# Audio_Tianfeng2.net
KiCad netlist of a schematic drawn in EAGLE
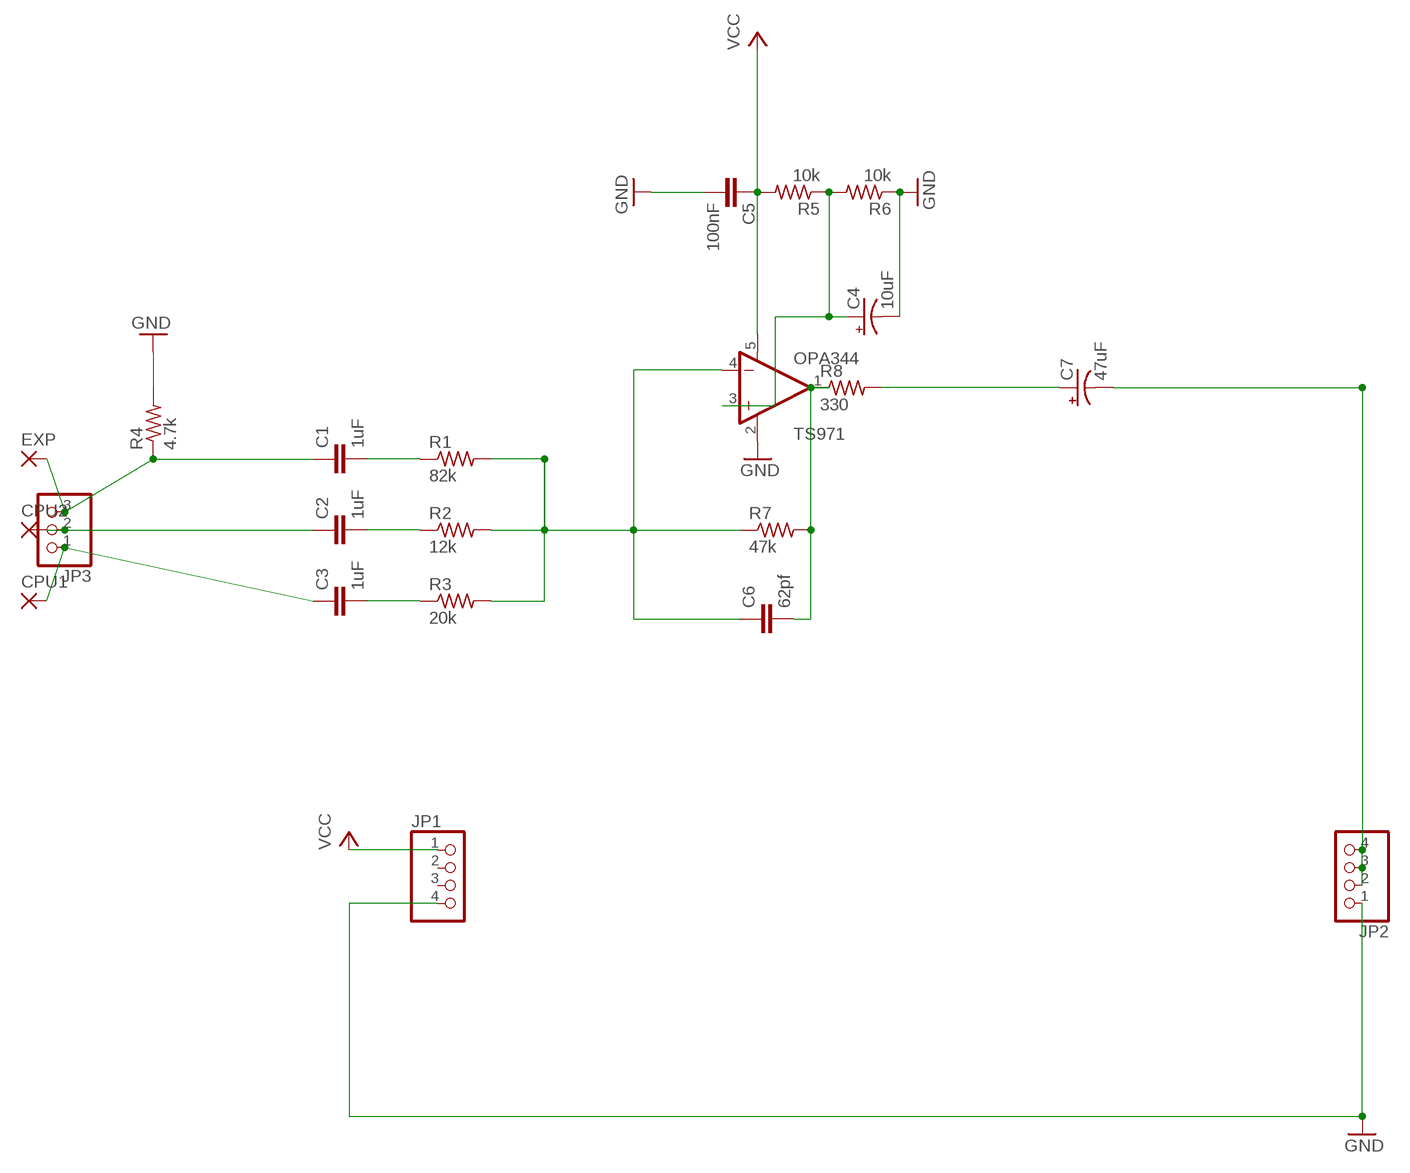
[diagram p0: schematic, sheet 1]

(export (version "E")
  (design (tool "Eeschema 10.0.6"))
  (components
    (comp (ref "C1")
      (value "1uF")
      (footprint "eagle-import:C0603K")
      (libsource (lib "eagle-import") (part "C-EUC0603K"))
    )
    (comp (ref "C2")
      (value "1uF")
      (footprint "eagle-import:C0603K")
      (libsource (lib "eagle-import") (part "C-EUC0603K"))
    )
    (comp (ref "C3")
      (value "1uF")
      (footprint "eagle-import:C0603K")
      (libsource (lib "eagle-import") (part "C-EUC0603K"))
    )
    (comp (ref "C4")
      (value "10uF")
      (footprint "eagle-import:153CLV-0405")
      (libsource (lib "eagle-import") (part "CPOL-US153CLV-0405"))
    )
    (comp (ref "C5")
      (value "100nF")
      (footprint "eagle-import:C0603K")
      (libsource (lib "eagle-import") (part "C-EUC0603K"))
    )
    (comp (ref "C6")
      (value "62pf")
      (footprint "eagle-import:C0603K")
      (libsource (lib "eagle-import") (part "C-EUC0603K"))
    )
    (comp (ref "C7")
      (value "47uF")
      (footprint "eagle-import:153CLV-0405")
      (libsource (lib "eagle-import") (part "CPOL-US153CLV-0405"))
    )
    (comp (ref "CPU1")
      (value "SMD2")
      (footprint "eagle-import:SMD1,27-2,54")
      (libsource (lib "eagle-import") (part "SMD2"))
    )
    (comp (ref "CPU2")
      (value "SMD2")
      (footprint "eagle-import:SMD1,27-2,54")
      (libsource (lib "eagle-import") (part "SMD2"))
    )
    (comp (ref "EXP")
      (value "SMD2")
      (footprint "eagle-import:SMD1,27-2,54")
      (libsource (lib "eagle-import") (part "SMD2"))
    )
    (comp (ref "JP1")
      (value "PINHD-1X04_2.54-S")
      (footprint "eagle-import:1X04-S")
      (libsource (lib "eagle-import") (part "PINHD-1X04_2.54-S"))
    )
    (comp (ref "JP2")
      (value "PINHD-1X04_2.54-S")
      (footprint "eagle-import:1X04-S")
      (libsource (lib "eagle-import") (part "PINHD-1X04_2.54-S"))
    )
    (comp (ref "JP3")
      (value "PINHD-1X03_2.54-S")
      (footprint "eagle-import:1X03-S")
      (libsource (lib "eagle-import") (part "PINHD-1X03_2.54-S"))
    )
    (comp (ref "R1")
      (value "82k")
      (footprint "eagle-import:R0603")
      (libsource (lib "eagle-import") (part "R-US_R0603"))
    )
    (comp (ref "R2")
      (value "12k")
      (footprint "eagle-import:R0603")
      (libsource (lib "eagle-import") (part "R-US_R0603"))
    )
    (comp (ref "R3")
      (value "20k")
      (footprint "eagle-import:R0603")
      (libsource (lib "eagle-import") (part "R-US_R0603"))
    )
    (comp (ref "R4")
      (value "4.7k")
      (footprint "eagle-import:R0603")
      (libsource (lib "eagle-import") (part "R-US_R0603"))
    )
    (comp (ref "R5")
      (value "10k")
      (footprint "eagle-import:R0603")
      (libsource (lib "eagle-import") (part "R-US_R0603"))
    )
    (comp (ref "R6")
      (value "10k")
      (footprint "eagle-import:R0603")
      (libsource (lib "eagle-import") (part "R-US_R0603"))
    )
    (comp (ref "R7")
      (value "47k")
      (footprint "eagle-import:R0603")
      (libsource (lib "eagle-import") (part "R-US_R0603"))
    )
    (comp (ref "R8")
      (value "330")
      (footprint "eagle-import:R0603")
      (libsource (lib "eagle-import") (part "R-US_R0603"))
    )
    (comp (ref "TS971")
      (value "OPA344")
      (footprint "eagle-import:SOT23-5")
      (libsource (lib "eagle-import") (part "OPA344"))
    )
  )
  (nets
    (net (code "1") (name "GND") (class "Default")
      (node (ref "C4") (pin "-") (pinfunction "-_-") (pintype "passive"))
      (node (ref "C5") (pin "2") (pinfunction "2_2") (pintype "passive"))
      (node (ref "JP1") (pin "4") (pinfunction "4_4") (pintype "passive"))
      (node (ref "JP2") (pin "1") (pinfunction "1_1") (pintype "passive"))
      (node (ref "R4") (pin "2") (pinfunction "2_2") (pintype "passive"))
      (node (ref "R6") (pin "1") (pinfunction "1_1") (pintype "passive"))
      (node (ref "TS971") (pin "2") (pinfunction "V-_2") (pintype "power_in"))
    )
    (net (code "2") (name "Net-(C1-Pad2)") (class "Default")
      (node (ref "C1") (pin "2") (pinfunction "2_2") (pintype "passive"))
      (node (ref "R1") (pin "1") (pinfunction "1_1") (pintype "passive"))
    )
    (net (code "3") (name "Net-(C2-Pad2)") (class "Default")
      (node (ref "C2") (pin "2") (pinfunction "2_2") (pintype "passive"))
      (node (ref "R2") (pin "1") (pinfunction "1_1") (pintype "passive"))
    )
    (net (code "4") (name "Net-(C3-Pad2)") (class "Default")
      (node (ref "C3") (pin "2") (pinfunction "2_2") (pintype "passive"))
      (node (ref "R3") (pin "1") (pinfunction "1_1") (pintype "passive"))
    )
    (net (code "5") (name "Net-(C7-Pad+)") (class "Default")
      (node (ref "C7") (pin "+") (pinfunction "+_+") (pintype "passive"))
      (node (ref "R8") (pin "2") (pinfunction "2_2") (pintype "passive"))
    )
    (net (code "6") (name "Net-(C7-Pad-)") (class "Default")
      (node (ref "C7") (pin "-") (pinfunction "-_-") (pintype "passive"))
      (node (ref "JP2") (pin "2") (pinfunction "2_2") (pintype "passive"))
      (node (ref "JP2") (pin "3") (pinfunction "3_3") (pintype "passive"))
      (node (ref "JP2") (pin "4") (pinfunction "4_4") (pintype "passive"))
    )
    (net (code "7") (name "Net-(CPU1-P)") (class "Default")
      (node (ref "C3") (pin "1") (pinfunction "1_1") (pintype "passive"))
      (node (ref "CPU1") (pin "1") (pinfunction "P_1") (pintype "passive"))
      (node (ref "JP3") (pin "1") (pinfunction "1_1") (pintype "passive"))
    )
    (net (code "8") (name "Net-(CPU2-P)") (class "Default")
      (node (ref "C2") (pin "1") (pinfunction "1_1") (pintype "passive"))
      (node (ref "CPU2") (pin "1") (pinfunction "P_1") (pintype "passive"))
      (node (ref "JP3") (pin "2") (pinfunction "2_2") (pintype "passive"))
    )
    (net (code "9") (name "Net-(EXP-P)") (class "Default")
      (node (ref "C1") (pin "1") (pinfunction "1_1") (pintype "passive"))
      (node (ref "EXP") (pin "1") (pinfunction "P_1") (pintype "passive"))
      (node (ref "JP3") (pin "3") (pinfunction "3_3") (pintype "passive"))
      (node (ref "R4") (pin "1") (pinfunction "1_1") (pintype "passive"))
    )
    (net (code "10") (name "Net-(TS971-+IN)") (class "Default")
      (node (ref "C4") (pin "+") (pinfunction "+_+") (pintype "passive"))
      (node (ref "R5") (pin "1") (pinfunction "1_1") (pintype "passive"))
      (node (ref "R6") (pin "2") (pinfunction "2_2") (pintype "passive"))
      (node (ref "TS971") (pin "3") (pinfunction "+IN_3") (pintype "input"))
    )
    (net (code "11") (name "Net-(TS971--IN)") (class "Default")
      (node (ref "C6") (pin "1") (pinfunction "1_1") (pintype "passive"))
      (node (ref "R1") (pin "2") (pinfunction "2_2") (pintype "passive"))
      (node (ref "R2") (pin "2") (pinfunction "2_2") (pintype "passive"))
      (node (ref "R3") (pin "2") (pinfunction "2_2") (pintype "passive"))
      (node (ref "R7") (pin "1") (pinfunction "1_1") (pintype "passive"))
      (node (ref "TS971") (pin "4") (pinfunction "-IN_4") (pintype "input"))
    )
    (net (code "12") (name "Net-(TS971-OUT)") (class "Default")
      (node (ref "C6") (pin "2") (pinfunction "2_2") (pintype "passive"))
      (node (ref "R7") (pin "2") (pinfunction "2_2") (pintype "passive"))
      (node (ref "R8") (pin "1") (pinfunction "1_1") (pintype "passive"))
      (node (ref "TS971") (pin "1") (pinfunction "OUT_1") (pintype "output"))
    )
    (net (code "13") (name "VCC") (class "Default")
      (node (ref "C5") (pin "1") (pinfunction "1_1") (pintype "passive"))
      (node (ref "JP1") (pin "1") (pinfunction "1_1") (pintype "passive"))
      (node (ref "R5") (pin "2") (pinfunction "2_2") (pintype "passive"))
      (node (ref "TS971") (pin "5") (pinfunction "V+_5") (pintype "power_in"))
    )
    (net (code "14") (name "unconnected-(JP1-Pad2)") (class "Default")
      (node (ref "JP1") (pin "2") (pinfunction "2_2") (pintype "passive"))
    )
    (net (code "15") (name "unconnected-(JP1-Pad3)") (class "Default")
      (node (ref "JP1") (pin "3") (pinfunction "3_3") (pintype "passive"))
    )
  )
)
